# AtMega88.net
KiCad netlist of a schematic drawn in EAGLE
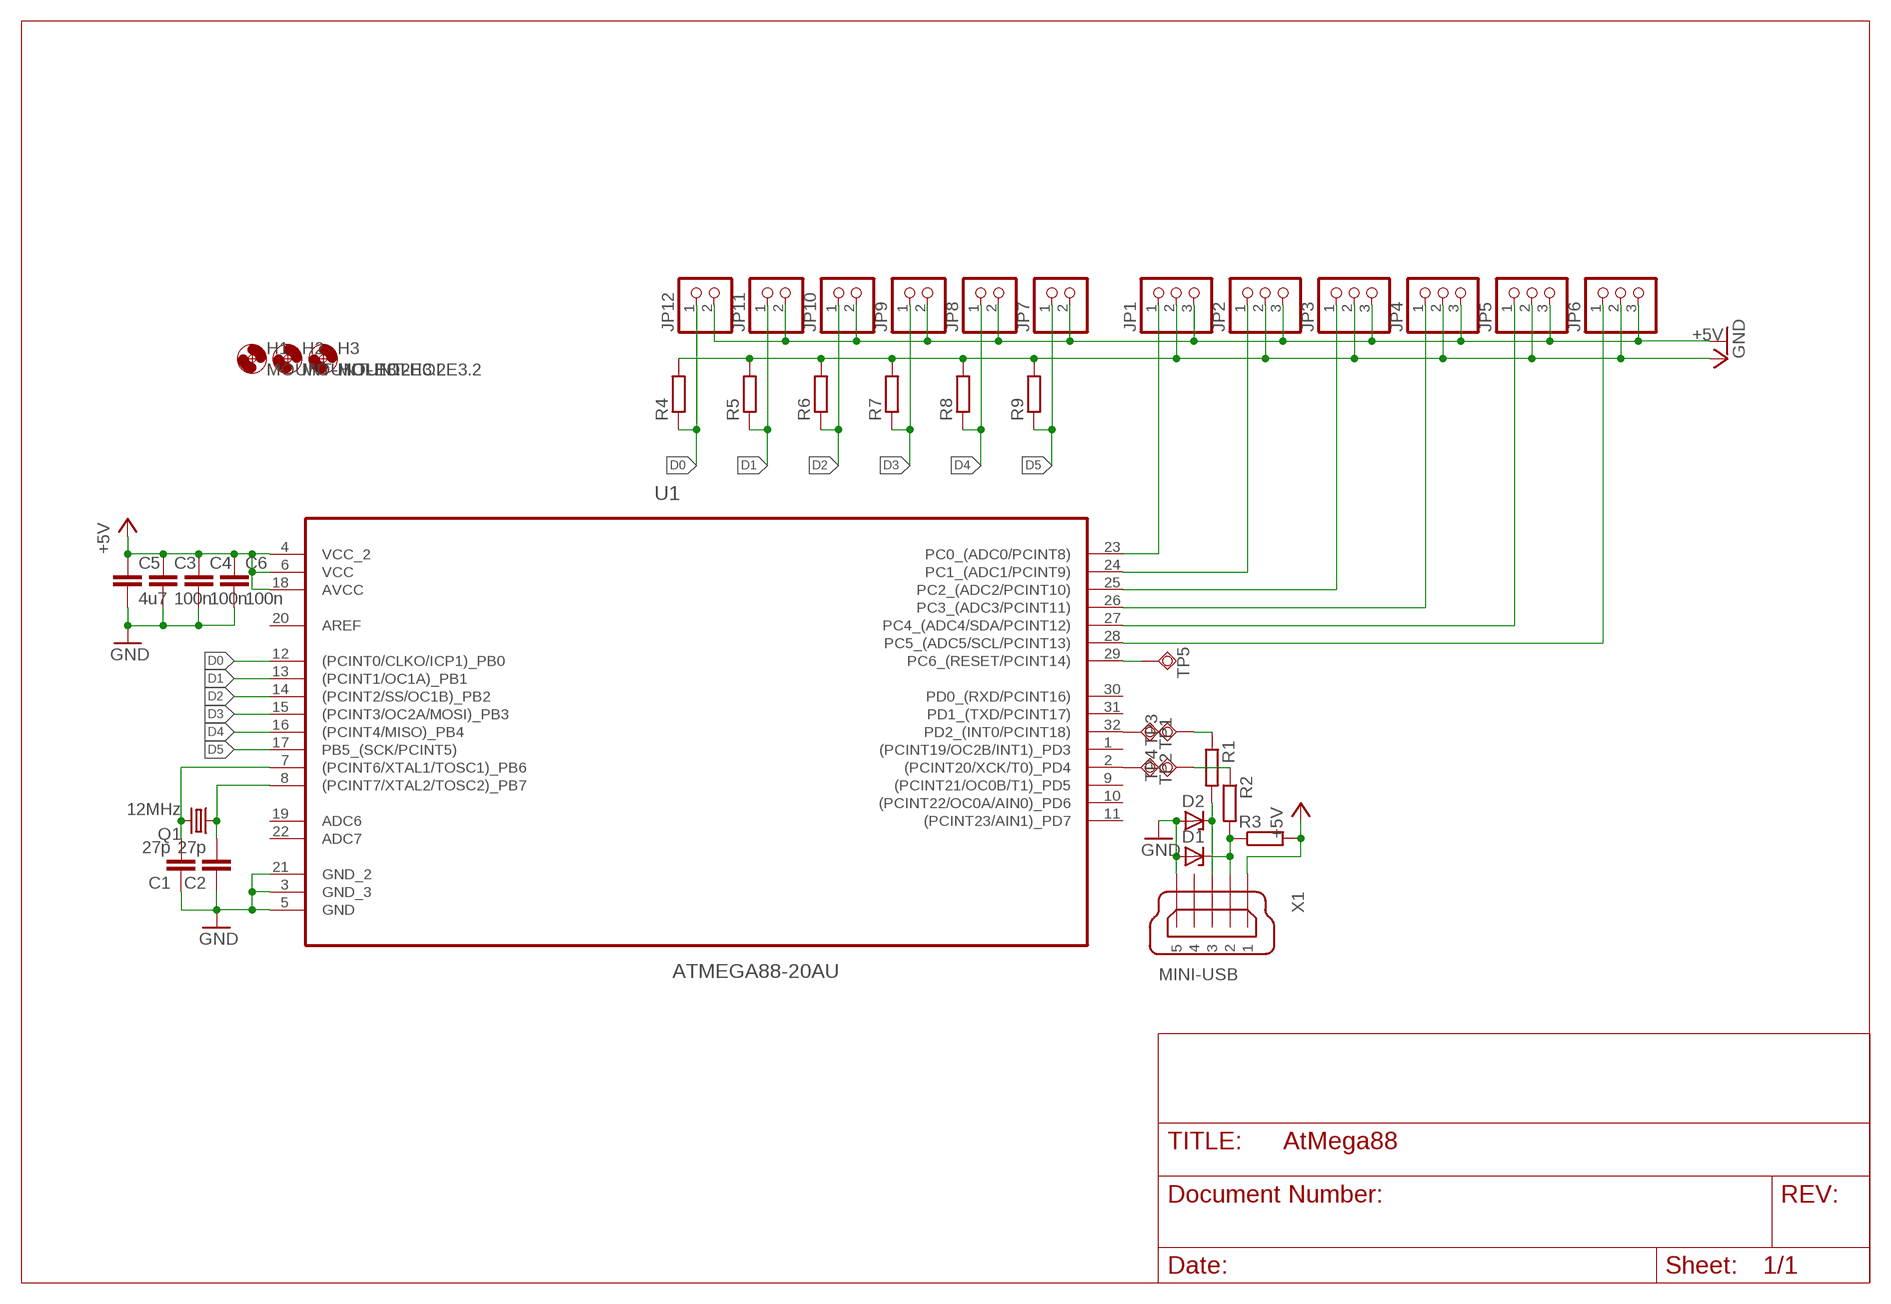
[diagram p0: schematic, sheet 1]

(export (version "E")
  (design (tool "Eeschema 10.0.6"))
  (components
    (comp (ref "C1")
      (value "27p")
      (footprint "eagle-import:C0805")
      (libsource (lib "eagle-import") (part "C-EUC0805"))
    )
    (comp (ref "C2")
      (value "27p")
      (footprint "eagle-import:C0805")
      (libsource (lib "eagle-import") (part "C-EUC0805"))
    )
    (comp (ref "C3")
      (value "100n")
      (footprint "eagle-import:C0805")
      (libsource (lib "eagle-import") (part "C-EUC0805"))
    )
    (comp (ref "C4")
      (value "100n")
      (footprint "eagle-import:C0805")
      (libsource (lib "eagle-import") (part "C-EUC0805"))
    )
    (comp (ref "C5")
      (value "4u7")
      (footprint "eagle-import:C0805")
      (libsource (lib "eagle-import") (part "C-EUC0805"))
    )
    (comp (ref "C6")
      (value "100n")
      (footprint "eagle-import:C0805")
      (libsource (lib "eagle-import") (part "C-EUC0805"))
    )
    (comp (ref "D1")
      (value "ZENER-DIODESOT23")
      (footprint "eagle-import:SOT23")
      (libsource (lib "eagle-import") (part "ZENER-DIODESOT23"))
    )
    (comp (ref "D2")
      (value "ZENER-DIODESOT23")
      (footprint "eagle-import:SOT23")
      (libsource (lib "eagle-import") (part "ZENER-DIODESOT23"))
    )
    (comp (ref "H1")
      (value "MOUNT-HOLE3.2")
      (footprint "eagle-import:3,2")
      (libsource (lib "eagle-import") (part "MOUNT-HOLE3.2"))
    )
    (comp (ref "H2")
      (value "MOUNT-HOLE3.2")
      (footprint "eagle-import:3,2")
      (libsource (lib "eagle-import") (part "MOUNT-HOLE3.2"))
    )
    (comp (ref "H3")
      (value "MOUNT-HOLE3.2")
      (footprint "eagle-import:3,2")
      (libsource (lib "eagle-import") (part "MOUNT-HOLE3.2"))
    )
    (comp (ref "JP1")
      (value "PINHD-1X3")
      (footprint "eagle-import:1X03")
      (libsource (lib "eagle-import") (part "PINHD-1X3"))
    )
    (comp (ref "JP2")
      (value "PINHD-1X3")
      (footprint "eagle-import:1X03")
      (libsource (lib "eagle-import") (part "PINHD-1X3"))
    )
    (comp (ref "JP3")
      (value "PINHD-1X3")
      (footprint "eagle-import:1X03")
      (libsource (lib "eagle-import") (part "PINHD-1X3"))
    )
    (comp (ref "JP4")
      (value "PINHD-1X3")
      (footprint "eagle-import:1X03")
      (libsource (lib "eagle-import") (part "PINHD-1X3"))
    )
    (comp (ref "JP5")
      (value "PINHD-1X3")
      (footprint "eagle-import:1X03")
      (libsource (lib "eagle-import") (part "PINHD-1X3"))
    )
    (comp (ref "JP6")
      (value "PINHD-1X3")
      (footprint "eagle-import:1X03")
      (libsource (lib "eagle-import") (part "PINHD-1X3"))
    )
    (comp (ref "JP7")
      (value "PINHD-1X2")
      (footprint "eagle-import:1X02")
      (libsource (lib "eagle-import") (part "PINHD-1X2"))
    )
    (comp (ref "JP8")
      (value "PINHD-1X2")
      (footprint "eagle-import:1X02")
      (libsource (lib "eagle-import") (part "PINHD-1X2"))
    )
    (comp (ref "JP9")
      (value "PINHD-1X2")
      (footprint "eagle-import:1X02")
      (libsource (lib "eagle-import") (part "PINHD-1X2"))
    )
    (comp (ref "JP10")
      (value "PINHD-1X2")
      (footprint "eagle-import:1X02")
      (libsource (lib "eagle-import") (part "PINHD-1X2"))
    )
    (comp (ref "JP11")
      (value "PINHD-1X2")
      (footprint "eagle-import:1X02")
      (libsource (lib "eagle-import") (part "PINHD-1X2"))
    )
    (comp (ref "JP12")
      (value "PINHD-1X2")
      (footprint "eagle-import:1X02")
      (libsource (lib "eagle-import") (part "PINHD-1X2"))
    )
    (comp (ref "Q1")
      (value "12MHz")
      (footprint "eagle-import:CSM-7X-DU")
      (libsource (lib "eagle-import") (part "CSM-7X-DU"))
    )
    (comp (ref "R1")
      (value "R-EU_R1206")
      (footprint "eagle-import:R1206")
      (libsource (lib "eagle-import") (part "R-EU_R1206"))
    )
    (comp (ref "R2")
      (value "R-EU_R1206")
      (footprint "eagle-import:R1206")
      (libsource (lib "eagle-import") (part "R-EU_R1206"))
    )
    (comp (ref "R3")
      (value "R-EU_R1206")
      (footprint "eagle-import:R1206")
      (libsource (lib "eagle-import") (part "R-EU_R1206"))
    )
    (comp (ref "R4")
      (value "R-EU_R1206")
      (footprint "eagle-import:R1206")
      (libsource (lib "eagle-import") (part "R-EU_R1206"))
    )
    (comp (ref "R5")
      (value "R-EU_R1206")
      (footprint "eagle-import:R1206")
      (libsource (lib "eagle-import") (part "R-EU_R1206"))
    )
    (comp (ref "R6")
      (value "R-EU_R1206")
      (footprint "eagle-import:R1206")
      (libsource (lib "eagle-import") (part "R-EU_R1206"))
    )
    (comp (ref "R7")
      (value "R-EU_R1206")
      (footprint "eagle-import:R1206")
      (libsource (lib "eagle-import") (part "R-EU_R1206"))
    )
    (comp (ref "R8")
      (value "R-EU_R1206")
      (footprint "eagle-import:R1206")
      (libsource (lib "eagle-import") (part "R-EU_R1206"))
    )
    (comp (ref "R9")
      (value "R-EU_R1206")
      (footprint "eagle-import:R1206")
      (libsource (lib "eagle-import") (part "R-EU_R1206"))
    )
    (comp (ref "TP1")
      (value "TPSQTP20SQ")
      (footprint "eagle-import:TP20SQ")
      (libsource (lib "eagle-import") (part "TPSQTP20SQ"))
    )
    (comp (ref "TP2")
      (value "TPSQTP20SQ")
      (footprint "eagle-import:TP20SQ")
      (libsource (lib "eagle-import") (part "TPSQTP20SQ"))
    )
    (comp (ref "TP3")
      (value "TPSQTP20SQ")
      (footprint "eagle-import:TP20SQ")
      (libsource (lib "eagle-import") (part "TPSQTP20SQ"))
    )
    (comp (ref "TP4")
      (value "TPSQTP20SQ")
      (footprint "eagle-import:TP20SQ")
      (libsource (lib "eagle-import") (part "TPSQTP20SQ"))
    )
    (comp (ref "TP5")
      (value "TPSQTP20SQ")
      (footprint "eagle-import:TP20SQ")
      (libsource (lib "eagle-import") (part "TPSQTP20SQ"))
    )
    (comp (ref "U1")
      (value "ATMEGA88-20AU")
      (footprint "eagle-import:QFP80P900X900X120-32N")
      (libsource (lib "eagle-import") (part "ATMEGA88-20AU"))
    )
    (comp (ref "X1")
      (value "MINI-USB")
      (footprint "eagle-import:UX60A-MB-5ST")
      (libsource (lib "eagle-import") (part "MINI-USB-UX60A-MB-5ST"))
    )
  )
  (nets
    (net (code "1") (name "+5V") (class "Default")
      (node (ref "C3") (pin "1") (pinfunction "1_1") (pintype "passive"))
      (node (ref "C4") (pin "1") (pinfunction "1_1") (pintype "passive"))
      (node (ref "C5") (pin "1") (pinfunction "1_1") (pintype "passive"))
      (node (ref "C6") (pin "1") (pinfunction "1_1") (pintype "passive"))
      (node (ref "JP1") (pin "2") (pinfunction "2_2") (pintype "passive"))
      (node (ref "JP2") (pin "2") (pinfunction "2_2") (pintype "passive"))
      (node (ref "JP3") (pin "2") (pinfunction "2_2") (pintype "passive"))
      (node (ref "JP4") (pin "2") (pinfunction "2_2") (pintype "passive"))
      (node (ref "JP5") (pin "2") (pinfunction "2_2") (pintype "passive"))
      (node (ref "JP6") (pin "2") (pinfunction "2_2") (pintype "passive"))
      (node (ref "R3") (pin "2") (pinfunction "2_2") (pintype "passive"))
      (node (ref "R4") (pin "2") (pinfunction "2_2") (pintype "passive"))
      (node (ref "R5") (pin "2") (pinfunction "2_2") (pintype "passive"))
      (node (ref "R6") (pin "2") (pinfunction "2_2") (pintype "passive"))
      (node (ref "R7") (pin "2") (pinfunction "2_2") (pintype "passive"))
      (node (ref "R8") (pin "2") (pinfunction "2_2") (pintype "passive"))
      (node (ref "R9") (pin "2") (pinfunction "2_2") (pintype "passive"))
      (node (ref "U1") (pin "18") (pinfunction "AVCC_18") (pintype "power_in"))
      (node (ref "U1") (pin "4") (pinfunction "VCC_2_4") (pintype "power_in"))
      (node (ref "U1") (pin "6") (pinfunction "VCC_6") (pintype "power_in"))
      (node (ref "X1") (pin "1") (pinfunction "1_1") (pintype "input"))
    )
    (net (code "2") (name "D0") (class "Default")
      (node (ref "JP12") (pin "1") (pinfunction "1_1") (pintype "passive"))
      (node (ref "R4") (pin "1") (pinfunction "1_1") (pintype "passive"))
      (node (ref "U1") (pin "12") (pinfunction "(PCINT0/CLKO/ICP1)_PB0_12") (pintype "bidirectional"))
    )
    (net (code "3") (name "D1") (class "Default")
      (node (ref "JP11") (pin "1") (pinfunction "1_1") (pintype "passive"))
      (node (ref "R5") (pin "1") (pinfunction "1_1") (pintype "passive"))
      (node (ref "U1") (pin "13") (pinfunction "(PCINT1/OC1A)_PB1_13") (pintype "bidirectional"))
    )
    (net (code "4") (name "D2") (class "Default")
      (node (ref "JP10") (pin "1") (pinfunction "1_1") (pintype "passive"))
      (node (ref "R6") (pin "1") (pinfunction "1_1") (pintype "passive"))
      (node (ref "U1") (pin "14") (pinfunction "(PCINT2/SS/OC1B)_PB2_14") (pintype "bidirectional"))
    )
    (net (code "5") (name "D3") (class "Default")
      (node (ref "JP9") (pin "1") (pinfunction "1_1") (pintype "passive"))
      (node (ref "R7") (pin "1") (pinfunction "1_1") (pintype "passive"))
      (node (ref "U1") (pin "15") (pinfunction "(PCINT3/OC2A/MOSI)_PB3_15") (pintype "bidirectional"))
    )
    (net (code "6") (name "D4") (class "Default")
      (node (ref "JP8") (pin "1") (pinfunction "1_1") (pintype "passive"))
      (node (ref "R8") (pin "1") (pinfunction "1_1") (pintype "passive"))
      (node (ref "U1") (pin "16") (pinfunction "(PCINT4/MISO)_PB4_16") (pintype "bidirectional"))
    )
    (net (code "7") (name "D5") (class "Default")
      (node (ref "JP7") (pin "1") (pinfunction "1_1") (pintype "passive"))
      (node (ref "R9") (pin "1") (pinfunction "1_1") (pintype "passive"))
      (node (ref "U1") (pin "17") (pinfunction "PB5_(SCK/PCINT5)_17") (pintype "bidirectional"))
    )
    (net (code "8") (name "GND") (class "Default")
      (node (ref "C1") (pin "1") (pinfunction "1_1") (pintype "passive"))
      (node (ref "C2") (pin "1") (pinfunction "1_1") (pintype "passive"))
      (node (ref "C3") (pin "2") (pinfunction "2_2") (pintype "passive"))
      (node (ref "C4") (pin "2") (pinfunction "2_2") (pintype "passive"))
      (node (ref "C5") (pin "2") (pinfunction "2_2") (pintype "passive"))
      (node (ref "C6") (pin "2") (pinfunction "2_2") (pintype "passive"))
      (node (ref "D1") (pin "1") (pinfunction "A_1") (pintype "passive"))
      (node (ref "D2") (pin "1") (pinfunction "A_1") (pintype "passive"))
      (node (ref "JP1") (pin "3") (pinfunction "3_3") (pintype "passive"))
      (node (ref "JP10") (pin "2") (pinfunction "2_2") (pintype "passive"))
      (node (ref "JP11") (pin "2") (pinfunction "2_2") (pintype "passive"))
      (node (ref "JP12") (pin "2") (pinfunction "2_2") (pintype "passive"))
      (node (ref "JP2") (pin "3") (pinfunction "3_3") (pintype "passive"))
      (node (ref "JP3") (pin "3") (pinfunction "3_3") (pintype "passive"))
      (node (ref "JP4") (pin "3") (pinfunction "3_3") (pintype "passive"))
      (node (ref "JP5") (pin "3") (pinfunction "3_3") (pintype "passive"))
      (node (ref "JP6") (pin "3") (pinfunction "3_3") (pintype "passive"))
      (node (ref "JP7") (pin "2") (pinfunction "2_2") (pintype "passive"))
      (node (ref "JP8") (pin "2") (pinfunction "2_2") (pintype "passive"))
      (node (ref "JP9") (pin "2") (pinfunction "2_2") (pintype "passive"))
      (node (ref "U1") (pin "21") (pinfunction "GND_2_21") (pintype "passive"))
      (node (ref "U1") (pin "3") (pinfunction "GND_3_3") (pintype "passive"))
      (node (ref "U1") (pin "5") (pinfunction "GND_5") (pintype "passive"))
      (node (ref "X1") (pin "5") (pinfunction "5_5") (pintype "input"))
    )
    (net (code "9") (name "Net-(D1-C)") (class "Default")
      (node (ref "D1") (pin "3") (pinfunction "C_3") (pintype "passive"))
      (node (ref "R2") (pin "2") (pinfunction "2_2") (pintype "passive"))
      (node (ref "R3") (pin "1") (pinfunction "1_1") (pintype "passive"))
      (node (ref "X1") (pin "2") (pinfunction "2_2") (pintype "input"))
    )
    (net (code "10") (name "Net-(D2-C)") (class "Default")
      (node (ref "D2") (pin "3") (pinfunction "C_3") (pintype "passive"))
      (node (ref "R1") (pin "2") (pinfunction "2_2") (pintype "passive"))
      (node (ref "X1") (pin "3") (pinfunction "3_3") (pintype "input"))
    )
    (net (code "11") (name "Net-(R1-Pad1)") (class "Default")
      (node (ref "R1") (pin "1") (pinfunction "1_1") (pintype "passive"))
      (node (ref "TP3") (pin "TP") (pinfunction "TP_TP") (pintype "input"))
    )
    (net (code "12") (name "Net-(R2-Pad1)") (class "Default")
      (node (ref "R2") (pin "1") (pinfunction "1_1") (pintype "passive"))
      (node (ref "TP4") (pin "TP") (pinfunction "TP_TP") (pintype "input"))
    )
    (net (code "13") (name "Net-(U1-(PCINT6{slash}XTAL1{slash}TOSC1)_PB6)") (class "Default")
      (node (ref "C1") (pin "2") (pinfunction "2_2") (pintype "passive"))
      (node (ref "Q1") (pin "2") (pinfunction "2_2") (pintype "passive"))
      (node (ref "U1") (pin "7") (pinfunction "(PCINT6/XTAL1/TOSC1)_PB6_7") (pintype "bidirectional"))
    )
    (net (code "14") (name "Net-(U1-(PCINT7{slash}XTAL2{slash}TOSC2)_PB7)") (class "Default")
      (node (ref "C2") (pin "2") (pinfunction "2_2") (pintype "passive"))
      (node (ref "Q1") (pin "1") (pinfunction "1_1") (pintype "passive"))
      (node (ref "U1") (pin "8") (pinfunction "(PCINT7/XTAL2/TOSC2)_PB7_8") (pintype "bidirectional"))
    )
    (net (code "15") (name "Net-(U1-(PCINT20{slash}XCK{slash}T0)_PD4)") (class "Default")
      (node (ref "TP2") (pin "TP") (pinfunction "TP_TP") (pintype "input"))
      (node (ref "U1") (pin "2") (pinfunction "(PCINT20/XCK/T0)_PD4_2") (pintype "bidirectional"))
    )
    (net (code "16") (name "Net-(U1-PC0_(ADC0{slash}PCINT8))") (class "Default")
      (node (ref "JP1") (pin "1") (pinfunction "1_1") (pintype "passive"))
      (node (ref "U1") (pin "23") (pinfunction "PC0_(ADC0/PCINT8)_23") (pintype "bidirectional"))
    )
    (net (code "17") (name "Net-(U1-PC1_(ADC1{slash}PCINT9))") (class "Default")
      (node (ref "JP2") (pin "1") (pinfunction "1_1") (pintype "passive"))
      (node (ref "U1") (pin "24") (pinfunction "PC1_(ADC1/PCINT9)_24") (pintype "bidirectional"))
    )
    (net (code "18") (name "Net-(U1-PC2_(ADC2{slash}PCINT10))") (class "Default")
      (node (ref "JP3") (pin "1") (pinfunction "1_1") (pintype "passive"))
      (node (ref "U1") (pin "25") (pinfunction "PC2_(ADC2/PCINT10)_25") (pintype "bidirectional"))
    )
    (net (code "19") (name "Net-(U1-PC3_(ADC3{slash}PCINT11))") (class "Default")
      (node (ref "JP4") (pin "1") (pinfunction "1_1") (pintype "passive"))
      (node (ref "U1") (pin "26") (pinfunction "PC3_(ADC3/PCINT11)_26") (pintype "bidirectional"))
    )
    (net (code "20") (name "Net-(U1-PC4_(ADC4{slash}SDA{slash}PCINT12))") (class "Default")
      (node (ref "JP5") (pin "1") (pinfunction "1_1") (pintype "passive"))
      (node (ref "U1") (pin "27") (pinfunction "PC4_(ADC4/SDA/PCINT12)_27") (pintype "bidirectional"))
    )
    (net (code "21") (name "Net-(U1-PC5_(ADC5{slash}SCL{slash}PCINT13))") (class "Default")
      (node (ref "JP6") (pin "1") (pinfunction "1_1") (pintype "passive"))
      (node (ref "U1") (pin "28") (pinfunction "PC5_(ADC5/SCL/PCINT13)_28") (pintype "bidirectional"))
    )
    (net (code "22") (name "Net-(U1-PC6_(RESET{slash}PCINT14))") (class "Default")
      (node (ref "TP5") (pin "TP") (pinfunction "TP_TP") (pintype "input"))
      (node (ref "U1") (pin "29") (pinfunction "PC6_(RESET/PCINT14)_29") (pintype "bidirectional"))
    )
    (net (code "23") (name "Net-(U1-PD2_(INT0{slash}PCINT18))") (class "Default")
      (node (ref "TP1") (pin "TP") (pinfunction "TP_TP") (pintype "input"))
      (node (ref "U1") (pin "32") (pinfunction "PD2_(INT0/PCINT18)_32") (pintype "bidirectional"))
    )
    (net (code "24") (name "unconnected-(U1-(PCINT19{slash}OC2B{slash}INT1)_PD3-Pad1)") (class "Default")
      (node (ref "U1") (pin "1") (pinfunction "(PCINT19/OC2B/INT1)_PD3_1") (pintype "bidirectional"))
    )
    (net (code "25") (name "unconnected-(U1-(PCINT21{slash}OC0B{slash}T1)_PD5-Pad9)") (class "Default")
      (node (ref "U1") (pin "9") (pinfunction "(PCINT21/OC0B/T1)_PD5_9") (pintype "bidirectional"))
    )
    (net (code "26") (name "unconnected-(U1-(PCINT22{slash}OC0A{slash}AIN0)_PD6-Pad10)") (class "Default")
      (node (ref "U1") (pin "10") (pinfunction "(PCINT22/OC0A/AIN0)_PD6_10") (pintype "bidirectional"))
    )
    (net (code "27") (name "unconnected-(U1-(PCINT23{slash}AIN1)_PD7-Pad11)") (class "Default")
      (node (ref "U1") (pin "11") (pinfunction "(PCINT23/AIN1)_PD7_11") (pintype "bidirectional"))
    )
    (net (code "28") (name "unconnected-(U1-ADC6-Pad19)") (class "Default")
      (node (ref "U1") (pin "19") (pinfunction "ADC6_19") (pintype "input"))
    )
    (net (code "29") (name "unconnected-(U1-ADC7-Pad22)") (class "Default")
      (node (ref "U1") (pin "22") (pinfunction "ADC7_22") (pintype "input"))
    )
    (net (code "30") (name "unconnected-(U1-AREF-Pad20)") (class "Default")
      (node (ref "U1") (pin "20") (pinfunction "AREF_20") (pintype "input"))
    )
    (net (code "31") (name "unconnected-(U1-PD0_(RXD{slash}PCINT16)-Pad30)") (class "Default")
      (node (ref "U1") (pin "30") (pinfunction "PD0_(RXD/PCINT16)_30") (pintype "bidirectional"))
    )
    (net (code "32") (name "unconnected-(U1-PD1_(TXD{slash}PCINT17)-Pad31)") (class "Default")
      (node (ref "U1") (pin "31") (pinfunction "PD1_(TXD/PCINT17)_31") (pintype "bidirectional"))
    )
    (net (code "33") (name "unconnected-(X1-Pad4)") (class "Default")
      (node (ref "X1") (pin "4") (pinfunction "4_4") (pintype "input"))
    )
  )
)
